# Power_Switching_Circuit_rev5.net
KiCad netlist of a schematic drawn in EAGLE
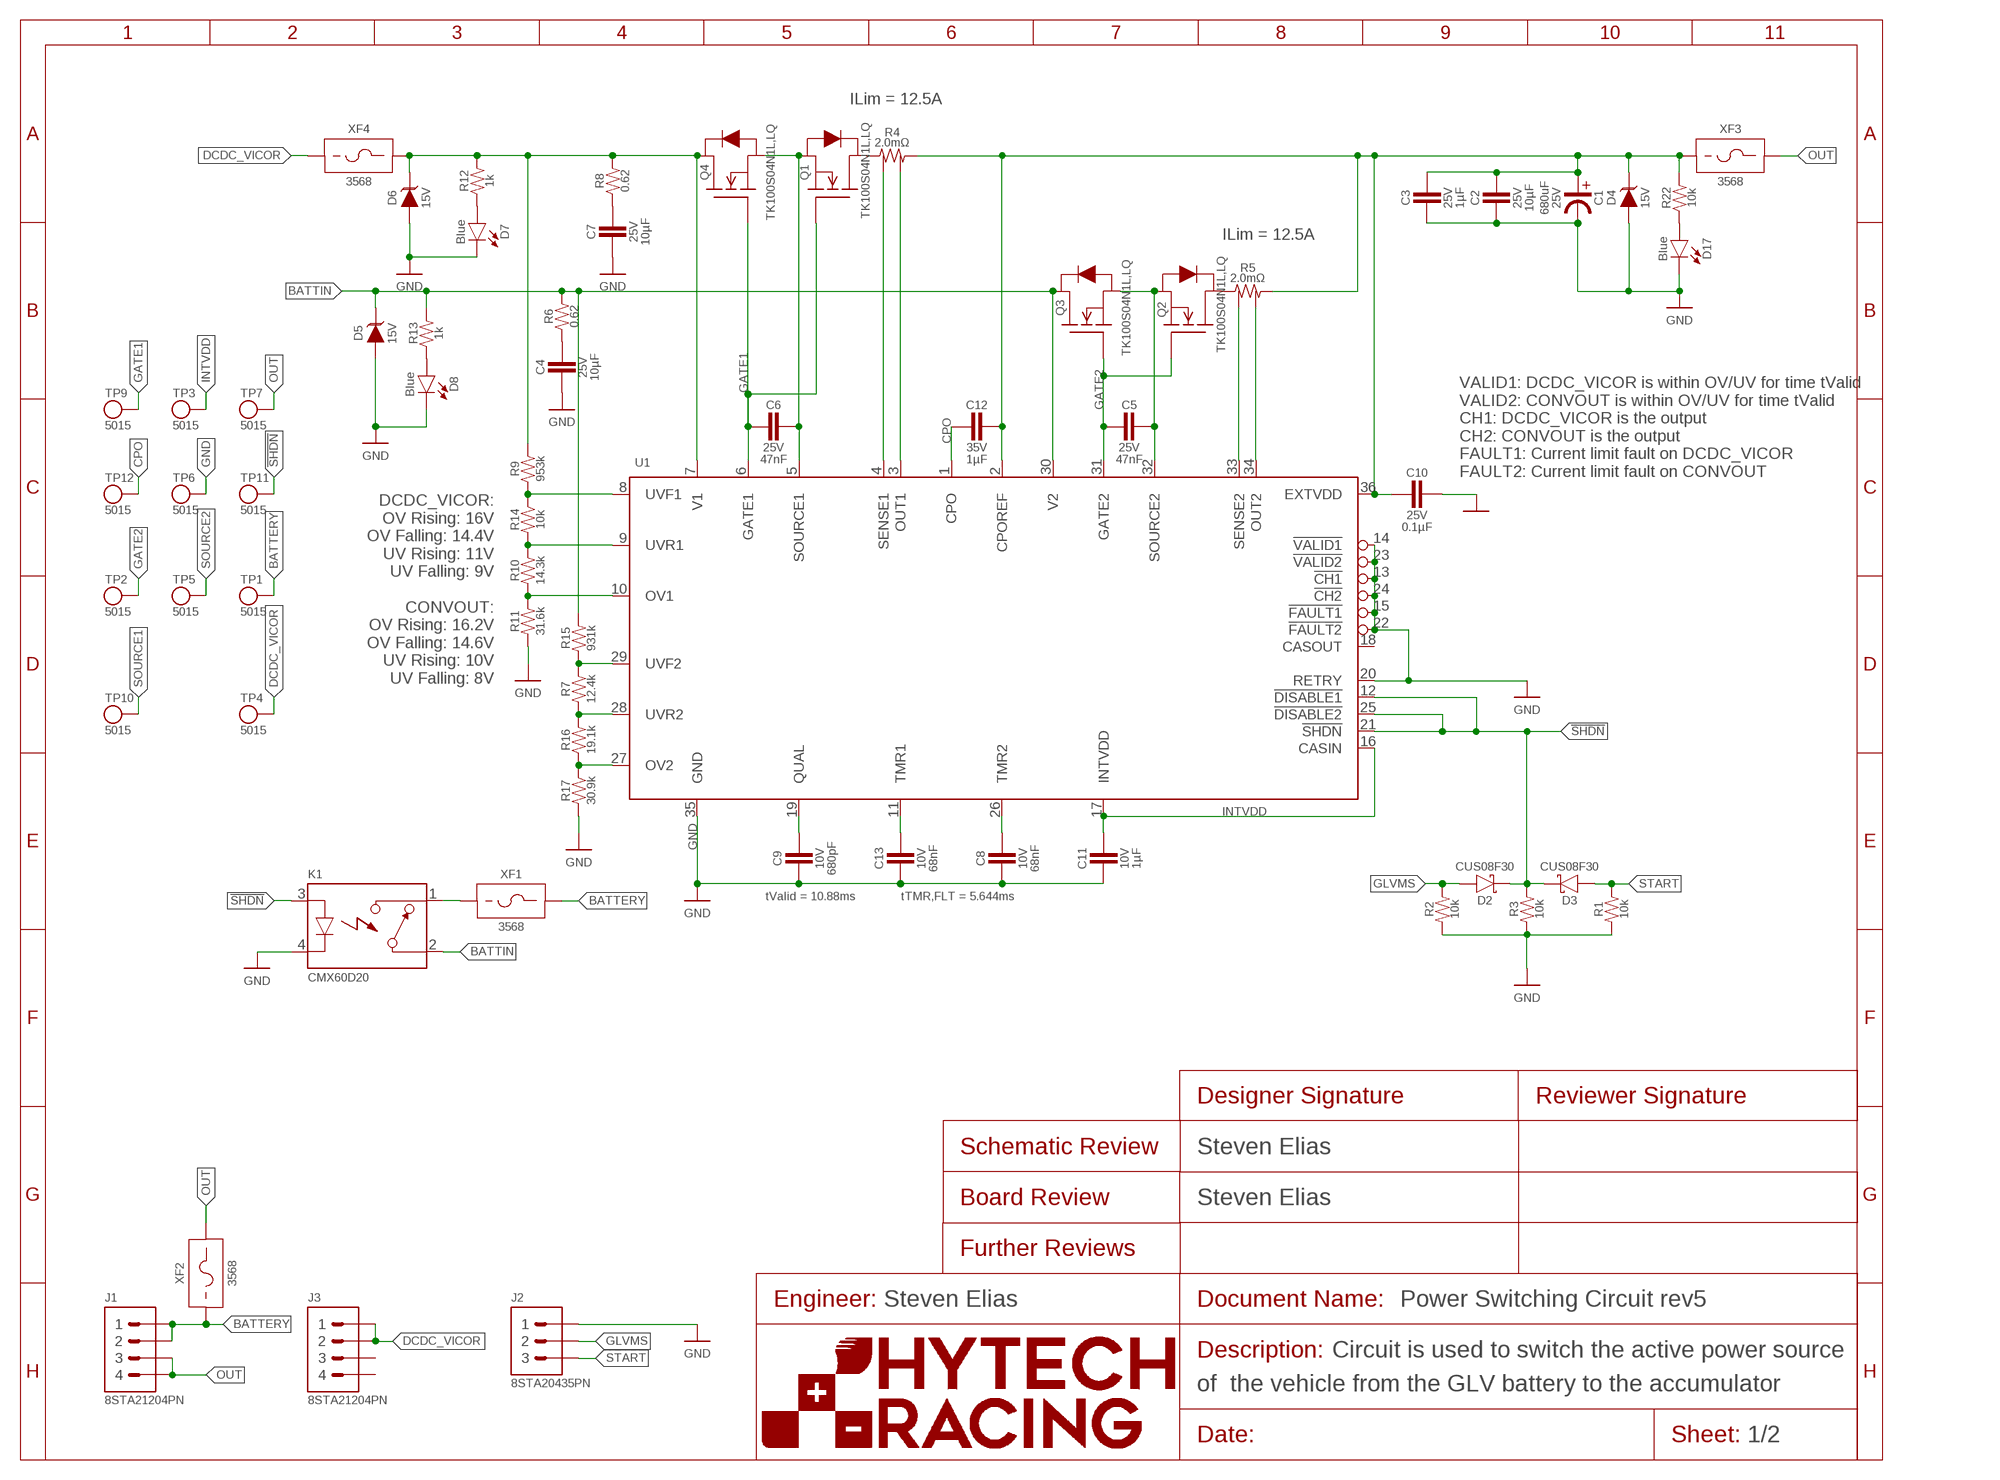
[diagram p0: schematic, sheet 1]
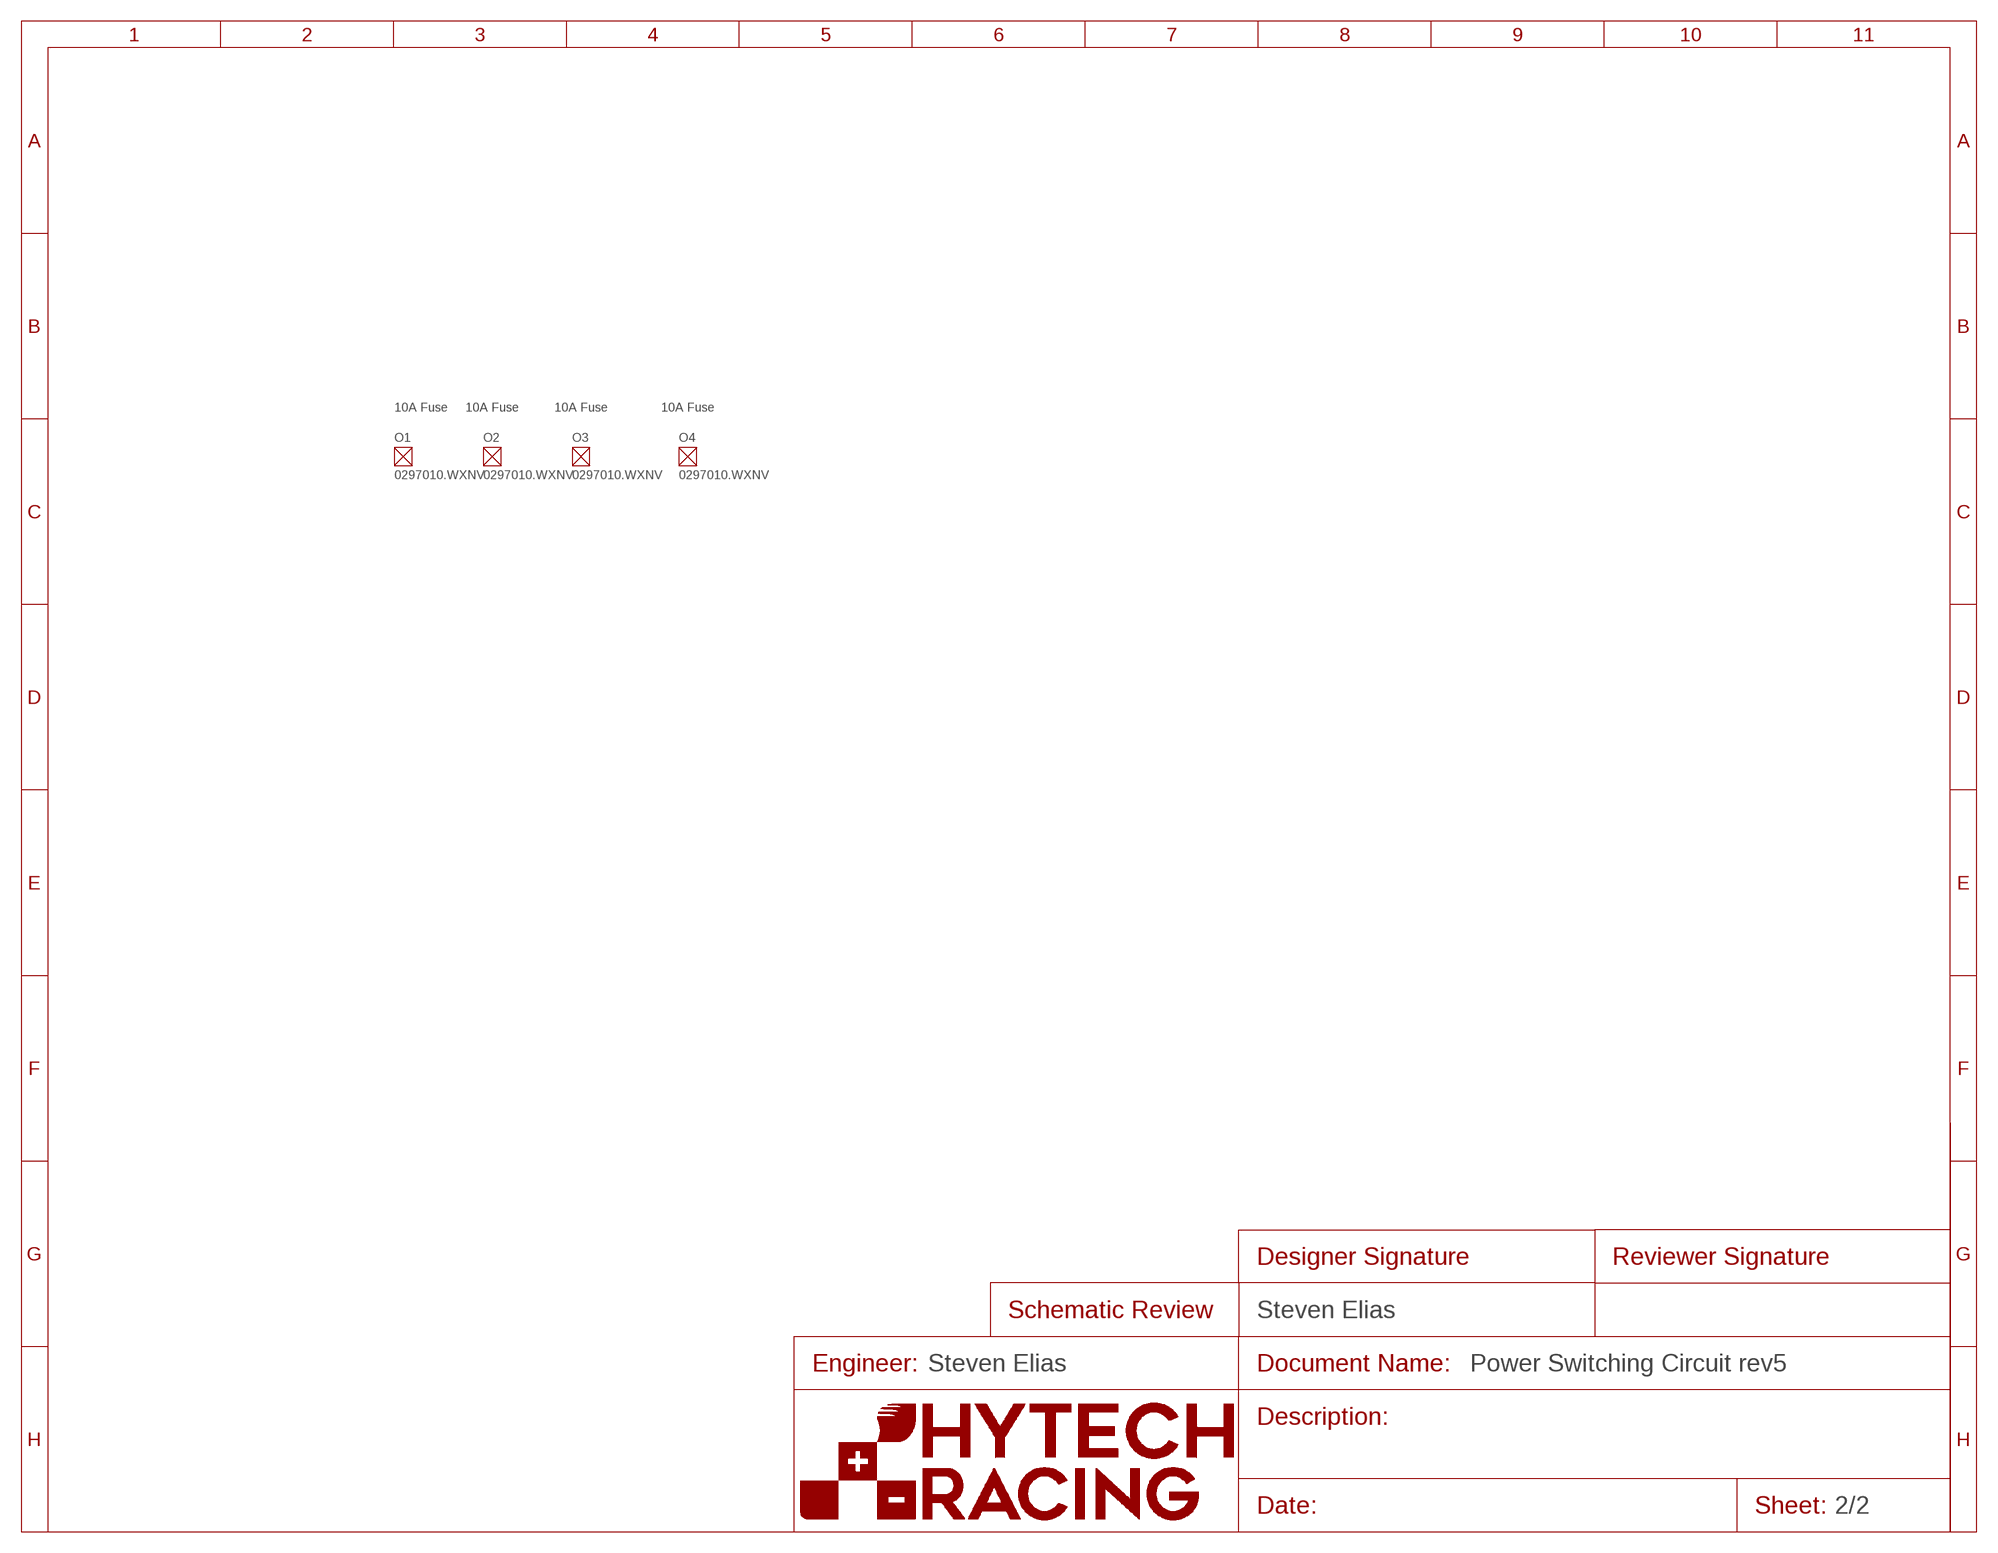
[diagram p1: schematic, sheet 2]

(export (version "E")
  (design (tool "Eeschema 10.0.6"))
  (components
    (comp (ref "C1")
      (value "EEUFP1E681")
      (footprint "eagle-import:EEUFP1E_")
      (fields
        (field (name "CAPACITANCE") "680uF")
        (field (name "MANUFACTURER") "Panasonic Electronic Components")
        (field (name "MPN") "EEU-FP1E681")
        (field (name "TOLERANCE") "20%")
        (field (name "VOLTAGE") "25V")
      )
      (libsource (lib "eagle-import") (part "EEUFP1E681"))
    )
    (comp (ref "C2")
      (value "CAPACITOR_0603_25V_10UF")
      (footprint "eagle-import:0603-CAP")
      (fields
        (field (name "CAPACITANCE") "10µF")
        (field (name "MANUFACTURER") "Murata Electronics")
        (field (name "MPN") "GRM188R61E106MA73D")
        (field (name "TOLERANCE") "20%")
        (field (name "VOLTAGE") "25V")
      )
      (libsource (lib "eagle-import") (part "CAPACITOR_?_060325V_10UF"))
    )
    (comp (ref "C3")
      (value "CAPACITOR_0603_25V_1UF")
      (footprint "eagle-import:0603-CAP")
      (fields
        (field (name "CAPACITANCE") "1µF")
        (field (name "MANUFACTURER") "Samsung Electro-Mechanics")
        (field (name "MPN") "CL10B105KA8NNNC")
        (field (name "TOLERANCE") "10%")
        (field (name "VOLTAGE") "25V")
      )
      (libsource (lib "eagle-import") (part "CAPACITOR_?_060325V_1UF"))
    )
    (comp (ref "C4")
      (value "CAPACITOR_0603_25V_10UF")
      (footprint "eagle-import:0603-CAP")
      (fields
        (field (name "CAPACITANCE") "10µF")
        (field (name "MANUFACTURER") "Murata Electronics")
        (field (name "MPN") "GRM188R61E106MA73D")
        (field (name "TOLERANCE") "20%")
        (field (name "VOLTAGE") "25V")
      )
      (libsource (lib "eagle-import") (part "CAPACITOR_?_060325V_10UF"))
    )
    (comp (ref "C5")
      (value "CAPACITOR_0603_25V_47NF")
      (footprint "eagle-import:0603-CAP")
      (fields
        (field (name "CAPACITANCE") "47nF")
        (field (name "MANUFACTURER") "Kyocera AVX")
        (field (name "MPN") "06033C473K4Z2A")
        (field (name "TOLERANCE") "10%")
        (field (name "VOLTAGE") "25V")
      )
      (libsource (lib "eagle-import") (part "CAPACITOR_?_060325V_47NF"))
    )
    (comp (ref "C6")
      (value "CAPACITOR_0603_25V_47NF")
      (footprint "eagle-import:0603-CAP")
      (fields
        (field (name "CAPACITANCE") "47nF")
        (field (name "MANUFACTURER") "Kyocera AVX")
        (field (name "MPN") "06033C473K4Z2A")
        (field (name "TOLERANCE") "10%")
        (field (name "VOLTAGE") "25V")
      )
      (libsource (lib "eagle-import") (part "CAPACITOR_?_060325V_47NF"))
    )
    (comp (ref "C7")
      (value "CAPACITOR_0603_25V_10UF")
      (footprint "eagle-import:0603-CAP")
      (fields
        (field (name "CAPACITANCE") "10µF")
        (field (name "MANUFACTURER") "Murata Electronics")
        (field (name "MPN") "GRM188R61E106MA73D")
        (field (name "TOLERANCE") "20%")
        (field (name "VOLTAGE") "25V")
      )
      (libsource (lib "eagle-import") (part "CAPACITOR_?_060325V_10UF"))
    )
    (comp (ref "C8")
      (value "CAPACITOR_0603_10V_68NF")
      (footprint "eagle-import:0603-CAP")
      (fields
        (field (name "CAPACITANCE") "68nF")
        (field (name "MANUFACTURER") "KEMET")
        (field (name "MPN") "C0603C683K8RACTU")
        (field (name "TOLERANCE") "10%")
        (field (name "VOLTAGE") "10V")
      )
      (libsource (lib "eagle-import") (part "CAPACITOR_?_060310V_68NF"))
    )
    (comp (ref "C9")
      (value "CAPACITOR_0603_10V_680PF")
      (footprint "eagle-import:0603-CAP")
      (fields
        (field (name "CAPACITANCE") "680pF")
        (field (name "MANUFACTURER") "Würth Elektronik")
        (field (name "MPN") "885012006013")
        (field (name "TOLERANCE") "5%")
        (field (name "VOLTAGE") "10V")
      )
      (libsource (lib "eagle-import") (part "CAPACITOR_?_060310V_680PF"))
    )
    (comp (ref "C10")
      (value "CAPACITOR_0603_25V_0.1UF")
      (footprint "eagle-import:0603-CAP")
      (fields
        (field (name "CAPACITANCE") "0.1µF")
        (field (name "MANUFACTURER") "Samsung Electro-Mechanics")
        (field (name "MPN") "CL10B104KA8NNNC")
        (field (name "TOLERANCE") "10%")
        (field (name "VOLTAGE") "25V")
      )
      (libsource (lib "eagle-import") (part "CAPACITOR_?_060325V_0.1UF"))
    )
    (comp (ref "C11")
      (value "CAPACITOR_0603_10V_1UF")
      (footprint "eagle-import:0603-CAP")
      (fields
        (field (name "CAPACITANCE") "1µF")
        (field (name "MANUFACTURER") "Yageo")
        (field (name "MPN") "CC0603KRX7R6BB105")
        (field (name "TOLERANCE") "10%")
        (field (name "VOLTAGE") "10V")
      )
      (libsource (lib "eagle-import") (part "CAPACITOR_?_060310V_1UF"))
    )
    (comp (ref "C12")
      (value "CAPACITOR_0603_35V_1UF")
      (footprint "eagle-import:0603-CAP")
      (fields
        (field (name "CAPACITANCE") "1µF")
        (field (name "MANUFACTURER") "TDK Corporation")
        (field (name "MPN") "C1608X7R1V105K080AE")
        (field (name "TOLERANCE") "10%")
        (field (name "VOLTAGE") "35V")
      )
      (libsource (lib "eagle-import") (part "CAPACITOR_?_060335V_1UF"))
    )
    (comp (ref "C13")
      (value "CAPACITOR_0603_10V_68NF")
      (footprint "eagle-import:0603-CAP")
      (fields
        (field (name "CAPACITANCE") "68nF")
        (field (name "MANUFACTURER") "KEMET")
        (field (name "MPN") "C0603C683K8RACTU")
        (field (name "TOLERANCE") "10%")
        (field (name "VOLTAGE") "10V")
      )
      (libsource (lib "eagle-import") (part "CAPACITOR_?_060310V_68NF"))
    )
    (comp (ref "D2")
      (value "SCHOTTKY_SOD323_30V")
      (footprint "eagle-import:SOD-323")
      (fields
        (field (name "MANUFACTURER") "Toshiba Semiconductor and Storage")
        (field (name "MPN") "CUS08F30")
        (field (name "VOLTAGE") "30V")
      )
      (libsource (lib "eagle-import") (part "SCHOTTKY_?_SOD32330V"))
    )
    (comp (ref "D3")
      (value "SCHOTTKY_SOD323_30V")
      (footprint "eagle-import:SOD-323")
      (fields
        (field (name "MANUFACTURER") "Toshiba Semiconductor and Storage")
        (field (name "MPN") "CUS08F30")
        (field (name "VOLTAGE") "30V")
      )
      (libsource (lib "eagle-import") (part "SCHOTTKY_?_SOD32330V"))
    )
    (comp (ref "D4")
      (value "TVS_15V")
      (footprint "eagle-import:SOT-23")
      (fields
        (field (name "MANUFACTURER") "Vishay General Semiconductor - Diodes Division")
        (field (name "MPN") "GSOT15-E3-08")
        (field (name "VOLTAGE") "15V")
      )
      (libsource (lib "eagle-import") (part "TVS_15V"))
    )
    (comp (ref "D5")
      (value "TVS_15V")
      (footprint "eagle-import:SOT-23")
      (fields
        (field (name "MANUFACTURER") "Vishay General Semiconductor - Diodes Division")
        (field (name "MPN") "GSOT15-E3-08")
        (field (name "VOLTAGE") "15V")
      )
      (libsource (lib "eagle-import") (part "TVS_15V"))
    )
    (comp (ref "D6")
      (value "TVS_15V")
      (footprint "eagle-import:SOT-23")
      (fields
        (field (name "MANUFACTURER") "Vishay General Semiconductor - Diodes Division")
        (field (name "MPN") "GSOT15-E3-08")
        (field (name "VOLTAGE") "15V")
      )
      (libsource (lib "eagle-import") (part "TVS_15V"))
    )
    (comp (ref "D7")
      (value "LED_0603_BLUE")
      (footprint "eagle-import:0603-LED")
      (fields
        (field (name "COLOR") "Blue")
        (field (name "MANUFACTURER") "Kingbright")
        (field (name "MPN") "APT1608VBC/D")
      )
      (libsource (lib "eagle-import") (part "LED_?_0603BLUE"))
    )
    (comp (ref "D8")
      (value "LED_0603_BLUE")
      (footprint "eagle-import:0603-LED")
      (fields
        (field (name "COLOR") "Blue")
        (field (name "MANUFACTURER") "Kingbright")
        (field (name "MPN") "APT1608VBC/D")
      )
      (libsource (lib "eagle-import") (part "LED_?_0603BLUE"))
    )
    (comp (ref "D17")
      (value "LED_0603_BLUE")
      (footprint "eagle-import:0603-LED")
      (fields
        (field (name "COLOR") "Blue")
        (field (name "MANUFACTURER") "Kingbright")
        (field (name "MPN") "APT1608VBC/D")
      )
      (libsource (lib "eagle-import") (part "LED_?_0603BLUE"))
    )
    (comp (ref "J1")
      (value "CONNECTOR-4_SOURIAU_")
      (footprint "eagle-import:SOURIAU_12-04")
      (fields (field (name "MPN") "8STA21204PN") (field (name "MANUFACTURER") "Souriau"))
      (libsource (lib "eagle-import") (part "CONNECTOR-4_?_SOURIAU"))
    )
    (comp (ref "J2")
      (value "CONNECTOR-3_8STA20435PN")
      (footprint "eagle-import:SOURIAU_04-35")
      (fields (field (name "MANUFACTURER") "Souriau") (field (name "MPN") "8STA20435PN"))
      (libsource (lib "eagle-import") (part "CONNECTOR-3_?8STA20435PN"))
    )
    (comp (ref "J3")
      (value "CONNECTOR-4_SOURIAU_")
      (footprint "eagle-import:SOURIAU_12-04")
      (fields (field (name "MPN") "8STA21204PN") (field (name "MANUFACTURER") "Souriau"))
      (libsource (lib "eagle-import") (part "CONNECTOR-4_?_SOURIAU"))
    )
    (comp (ref "K1")
      (value "RELAY_SOLIDSTATE_NO_CMX60D20")
      (footprint "eagle-import:CRYDOM_CMX")
      (fields (field (name "MANUFACTURER") "Crydom") (field (name "MPN") "CMX60D20"))
      (libsource (lib "eagle-import") (part "RELAY_SOLIDSTATE_NO_?CMX60D20"))
    )
    (comp (ref "Q1")
      (value "TRANSISTOR_N_MOS_2-7K1S_TK100S04N1LLQ")
      (footprint "eagle-import:DPAK(2-7K1S)")
      (fields
        (field (name "MANUFACTURER") "Toshiba Semiconductor and Storage")
        (field (name "MPN") "TK100S04N1L,LQ")
      )
      (libsource (lib "eagle-import") (part "TRANSISTOR_N_MOS_?_2-7K1STK100S04N1LLQ"))
    )
    (comp (ref "Q2")
      (value "TRANSISTOR_N_MOS_2-7K1S_TK100S04N1LLQ")
      (footprint "eagle-import:DPAK(2-7K1S)")
      (fields
        (field (name "MANUFACTURER") "Toshiba Semiconductor and Storage")
        (field (name "MPN") "TK100S04N1L,LQ")
      )
      (libsource (lib "eagle-import") (part "TRANSISTOR_N_MOS_?_2-7K1STK100S04N1LLQ"))
    )
    (comp (ref "Q3")
      (value "TRANSISTOR_N_MOS_2-7K1S_TK100S04N1LLQ")
      (footprint "eagle-import:DPAK(2-7K1S)")
      (fields
        (field (name "MANUFACTURER") "Toshiba Semiconductor and Storage")
        (field (name "MPN") "TK100S04N1L,LQ")
      )
      (libsource (lib "eagle-import") (part "TRANSISTOR_N_MOS_?_2-7K1STK100S04N1LLQ"))
    )
    (comp (ref "Q4")
      (value "TRANSISTOR_N_MOS_2-7K1S_TK100S04N1LLQ")
      (footprint "eagle-import:DPAK(2-7K1S)")
      (fields
        (field (name "MANUFACTURER") "Toshiba Semiconductor and Storage")
        (field (name "MPN") "TK100S04N1L,LQ")
      )
      (libsource (lib "eagle-import") (part "TRANSISTOR_N_MOS_?_2-7K1STK100S04N1LLQ"))
    )
    (comp (ref "R1")
      (value "RESISTOR_0603_10K")
      (footprint "eagle-import:0603-RES")
      (fields
        (field (name "MANUFACTURER") "Yageo")
        (field (name "MPN") "RC0603FR-0710KL")
        (field (name "POWER") "0.1W")
        (field (name "RESISTANCE") "10k")
      )
      (libsource (lib "eagle-import") (part "RESISTOR_?_060310K"))
    )
    (comp (ref "R2")
      (value "RESISTOR_0603_10K")
      (footprint "eagle-import:0603-RES")
      (fields
        (field (name "MANUFACTURER") "Yageo")
        (field (name "MPN") "RC0603FR-0710KL")
        (field (name "POWER") "0.1W")
        (field (name "RESISTANCE") "10k")
      )
      (libsource (lib "eagle-import") (part "RESISTOR_?_060310K"))
    )
    (comp (ref "R3")
      (value "RESISTOR_0603_10K")
      (footprint "eagle-import:0603-RES")
      (fields
        (field (name "MANUFACTURER") "Yageo")
        (field (name "MPN") "RC0603FR-0710KL")
        (field (name "POWER") "0.1W")
        (field (name "RESISTANCE") "10k")
      )
      (libsource (lib "eagle-import") (part "RESISTOR_?_060310K"))
    )
    (comp (ref "R4")
      (value "RESISTOR_SENSE__WSL40262L000FEB")
      (footprint "eagle-import:4026")
      (fields
        (field (name "MANUFACTURER") "Vishay Dale")
        (field (name "MPN") "WSL40262L000FEB")
        (field (name "POWER") "3W")
        (field (name "RESISTANCE") "2.0mΩ")
      )
      (libsource (lib "eagle-import") (part "RESISTOR_SENSE_?_WSL40262L000FEB"))
    )
    (comp (ref "R5")
      (value "RESISTOR_SENSE__WSL40262L000FEB")
      (footprint "eagle-import:4026")
      (fields
        (field (name "MANUFACTURER") "Vishay Dale")
        (field (name "MPN") "WSL40262L000FEB")
        (field (name "POWER") "3W")
        (field (name "RESISTANCE") "2.0mΩ")
      )
      (libsource (lib "eagle-import") (part "RESISTOR_SENSE_?_WSL40262L000FEB"))
    )
    (comp (ref "R6")
      (value "RESISTOR_0805_0.62")
      (footprint "eagle-import:0805-RES")
      (fields
        (field (name "MANUFACTURER") "Yageo")
        (field (name "MPN") "RL0805FR-070R62L")
        (field (name "POWER") "0.125W")
        (field (name "RESISTANCE") "0.62")
      )
      (libsource (lib "eagle-import") (part "RESISTOR_?_08050.62"))
    )
    (comp (ref "R7")
      (value "RESISTOR_0603_12.4K")
      (footprint "eagle-import:0603-RES")
      (fields
        (field (name "MANUFACTURER") "Panasonic Electronic Components")
        (field (name "MPN") "ERJ-PB3B1242V")
        (field (name "POWER") "0.2W")
        (field (name "RESISTANCE") "12.4k")
      )
      (libsource (lib "eagle-import") (part "RESISTOR_?_060312.4K"))
    )
    (comp (ref "R8")
      (value "RESISTOR_0805_0.62")
      (footprint "eagle-import:0805-RES")
      (fields
        (field (name "MANUFACTURER") "Yageo")
        (field (name "MPN") "RL0805FR-070R62L")
        (field (name "POWER") "0.125W")
        (field (name "RESISTANCE") "0.62")
      )
      (libsource (lib "eagle-import") (part "RESISTOR_?_08050.62"))
    )
    (comp (ref "R9")
      (value "RESISTOR_0805_953K")
      (footprint "eagle-import:0805-RES")
      (fields
        (field (name "MANUFACTURER") "Panasonic Electronic Components")
        (field (name "MPN") "ERJ-6ENF9533V")
        (field (name "POWER") "0.125W")
        (field (name "RESISTANCE") "953k")
      )
      (libsource (lib "eagle-import") (part "RESISTOR_?_0805953K"))
    )
    (comp (ref "R10")
      (value "RESISTOR_0805_14.3K")
      (footprint "eagle-import:0805-RES")
      (fields
        (field (name "MANUFACTURER") "Panasonic Electronic Components")
        (field (name "MPN") "ERJ-6ENF1432V")
        (field (name "POWER") "0.125W")
        (field (name "RESISTANCE") "14.3k")
      )
      (libsource (lib "eagle-import") (part "RESISTOR_?_080514.3K"))
    )
    (comp (ref "R11")
      (value "RESISTOR_0805_31.6K")
      (footprint "eagle-import:0805-RES")
      (fields
        (field (name "MANUFACTURER") "Vishay Dale")
        (field (name "MPN") "CRCW060331K6FKEAHP")
        (field (name "POWER") "0.33W")
        (field (name "RESISTANCE") "31.6k")
      )
      (libsource (lib "eagle-import") (part "RESISTOR_?_080531.6K"))
    )
    (comp (ref "R12")
      (value "RESISTOR_0603_1K")
      (footprint "eagle-import:0603-RES")
      (fields
        (field (name "MANUFACTURER") "Yageo")
        (field (name "MPN") "RC0603FR-071KL")
        (field (name "POWER") "0.1W")
        (field (name "RESISTANCE") "1k")
      )
      (libsource (lib "eagle-import") (part "RESISTOR_?_06031K"))
    )
    (comp (ref "R13")
      (value "RESISTOR_0603_1K")
      (footprint "eagle-import:0603-RES")
      (fields
        (field (name "MANUFACTURER") "Yageo")
        (field (name "MPN") "RC0603FR-071KL")
        (field (name "POWER") "0.1W")
        (field (name "RESISTANCE") "1k")
      )
      (libsource (lib "eagle-import") (part "RESISTOR_?_06031K"))
    )
    (comp (ref "R14")
      (value "RESISTOR_0603_10K")
      (footprint "eagle-import:0603-RES")
      (fields
        (field (name "MANUFACTURER") "Yageo")
        (field (name "MPN") "RC0603FR-0710KL")
        (field (name "POWER") "0.1W")
        (field (name "RESISTANCE") "10k")
      )
      (libsource (lib "eagle-import") (part "RESISTOR_?_060310K"))
    )
    (comp (ref "R15")
      (value "RESISTOR_0805_931K")
      (footprint "eagle-import:0805-RES")
      (fields
        (field (name "MANUFACTURER") "Panasonic Electronic Components")
        (field (name "MPN") "ERJ-PB6B9313V")
        (field (name "POWER") "0.25W")
        (field (name "RESISTANCE") "931k")
      )
      (libsource (lib "eagle-import") (part "RESISTOR_?_0805931K"))
    )
    (comp (ref "R16")
      (value "RESISTOR_0805_19.1K")
      (footprint "eagle-import:0805-RES")
      (fields
        (field (name "MANUFACTURER") "Panasonic Electronic Components")
        (field (name "MPN") "ERJ-6ENF1912V")
        (field (name "POWER") "0.125W")
        (field (name "RESISTANCE") "19.1k")
      )
      (libsource (lib "eagle-import") (part "RESISTOR_?_080519.1K"))
    )
    (comp (ref "R17")
      (value "RESISTOR_0603_30.9K")
      (footprint "eagle-import:0603-RES")
      (fields
        (field (name "MANUFACTURER") "Panasonic Electronic Components")
        (field (name "MPN") "ERJ-PB3B3092V")
        (field (name "POWER") "0.25W")
        (field (name "RESISTANCE") "30.9k")
      )
      (libsource (lib "eagle-import") (part "RESISTOR_?_060330.9K"))
    )
    (comp (ref "R22")
      (value "RESISTOR_0603_10K")
      (footprint "eagle-import:0603-RES")
      (fields
        (field (name "MANUFACTURER") "Yageo")
        (field (name "MPN") "RC0603FR-0710KL")
        (field (name "POWER") "0.1W")
        (field (name "RESISTANCE") "10k")
      )
      (libsource (lib "eagle-import") (part "RESISTOR_?_060310K"))
    )
    (comp (ref "TP1")
      (value "TEST_POINT")
      (footprint "eagle-import:5015")
      (fields (field (name "MPN") "5015") (field (name "MANUFACTURER") "Keystone Electronics"))
      (libsource (lib "eagle-import") (part "TEST_POINT"))
    )
    (comp (ref "TP2")
      (value "TEST_POINT")
      (footprint "eagle-import:5015")
      (fields (field (name "MPN") "5015") (field (name "MANUFACTURER") "Keystone Electronics"))
      (libsource (lib "eagle-import") (part "TEST_POINT"))
    )
    (comp (ref "TP3")
      (value "INTVDD")
      (footprint "eagle-import:5015")
      (fields (field (name "MPN") "5015") (field (name "MANUFACTURER") "Keystone Electronics"))
      (libsource (lib "eagle-import") (part "TEST_POINT"))
    )
    (comp (ref "TP4")
      (value "TEST_POINT")
      (footprint "eagle-import:5015")
      (fields (field (name "MPN") "5015") (field (name "MANUFACTURER") "Keystone Electronics"))
      (libsource (lib "eagle-import") (part "TEST_POINT"))
    )
    (comp (ref "TP5")
      (value "TEST_POINT")
      (footprint "eagle-import:5015")
      (fields (field (name "MPN") "5015") (field (name "MANUFACTURER") "Keystone Electronics"))
      (libsource (lib "eagle-import") (part "TEST_POINT"))
    )
    (comp (ref "TP6")
      (value "TEST_POINT")
      (footprint "eagle-import:5015")
      (fields (field (name "MPN") "5015") (field (name "MANUFACTURER") "Keystone Electronics"))
      (libsource (lib "eagle-import") (part "TEST_POINT"))
    )
    (comp (ref "TP7")
      (value "TEST_POINT")
      (footprint "eagle-import:5015")
      (fields (field (name "MPN") "5015") (field (name "MANUFACTURER") "Keystone Electronics"))
      (libsource (lib "eagle-import") (part "TEST_POINT"))
    )
    (comp (ref "TP9")
      (value "TEST_POINT")
      (footprint "eagle-import:5015")
      (fields (field (name "MPN") "5015") (field (name "MANUFACTURER") "Keystone Electronics"))
      (libsource (lib "eagle-import") (part "TEST_POINT"))
    )
    (comp (ref "TP10")
      (value "TEST_POINT")
      (footprint "eagle-import:5015")
      (fields (field (name "MPN") "5015") (field (name "MANUFACTURER") "Keystone Electronics"))
      (libsource (lib "eagle-import") (part "TEST_POINT"))
    )
    (comp (ref "TP11")
      (value "TEST_POINT")
      (footprint "eagle-import:5015")
      (fields (field (name "MPN") "5015") (field (name "MANUFACTURER") "Keystone Electronics"))
      (libsource (lib "eagle-import") (part "TEST_POINT"))
    )
    (comp (ref "TP12")
      (value "TEST_POINT")
      (footprint "eagle-import:5015")
      (fields (field (name "MPN") "5015") (field (name "MANUFACTURER") "Keystone Electronics"))
      (libsource (lib "eagle-import") (part "TEST_POINT"))
    )
    (comp (ref "U1")
      (value "LTC4421")
      (footprint "eagle-import:SSOP-36")
      (fields (field (name "MPN") "LTC4421CG#PBF") (field (name "MANUFACTURER") "Analog Devices Inc."))
      (libsource (lib "eagle-import") (part "LTC4421"))
    )
    (comp (ref "XF1")
      (value "FUSE_HOLDER_MINIBLADEPTH")
      (footprint "eagle-import:3568")
      (fields (field (name "MANUFACTURER") "Keystone") (field (name "MPN") "3568"))
      (libsource (lib "eagle-import") (part "FUSE_HOLDER_PTHMINIBLADE"))
    )
    (comp (ref "XF2")
      (value "FUSE_HOLDER_MINIBLADEPTH")
      (footprint "eagle-import:3568")
      (fields (field (name "MANUFACTURER") "Keystone") (field (name "MPN") "3568"))
      (libsource (lib "eagle-import") (part "FUSE_HOLDER_PTHMINIBLADE"))
    )
    (comp (ref "XF3")
      (value "FUSE_HOLDER_MINIBLADEPTH")
      (footprint "eagle-import:3568")
      (fields (field (name "MANUFACTURER") "Keystone") (field (name "MPN") "3568"))
      (libsource (lib "eagle-import") (part "FUSE_HOLDER_PTHMINIBLADE"))
    )
    (comp (ref "XF4")
      (value "FUSE_HOLDER_MINIBLADEPTH")
      (footprint "eagle-import:3568")
      (fields (field (name "MANUFACTURER") "Keystone") (field (name "MPN") "3568"))
      (libsource (lib "eagle-import") (part "FUSE_HOLDER_PTHMINIBLADE"))
    )
  )
  (nets
    (net (code "1") (name "BATTERY") (class "Default")
      (node (ref "J1") (pin "1") (pinfunction "1_1") (pintype "passive"))
      (node (ref "J1") (pin "2") (pinfunction "2_2") (pintype "passive"))
      (node (ref "TP1") (pin "1") (pinfunction "1_1") (pintype "passive"))
      (node (ref "XF1") (pin "3") (pinfunction "2_3") (pintype "passive"))
      (node (ref "XF1") (pin "4") (pinfunction "2_4") (pintype "passive"))
      (node (ref "XF2") (pin "1") (pinfunction "1_1") (pintype "passive"))
      (node (ref "XF2") (pin "2") (pinfunction "1_2") (pintype "passive"))
    )
    (net (code "2") (name "BATTIN") (class "Default")
      (node (ref "D5") (pin "3") (pinfunction "C_3") (pintype "passive"))
      (node (ref "K1") (pin "2") (pinfunction "CONTACT1_2") (pintype "bidirectional"))
      (node (ref "Q3") (pin "2") (pinfunction "D_2") (pintype "passive"))
      (node (ref "R13") (pin "2") (pinfunction "2_2") (pintype "passive"))
      (node (ref "R15") (pin "2") (pinfunction "2_2") (pintype "passive"))
      (node (ref "R6") (pin "2") (pinfunction "2_2") (pintype "passive"))
      (node (ref "U1") (pin "30") (pinfunction "V2_30") (pintype "input"))
    )
    (net (code "3") (name "CPO") (class "Default")
      (node (ref "C12") (pin "2") (pinfunction "2_2") (pintype "passive"))
      (node (ref "TP12") (pin "1") (pinfunction "1_1") (pintype "passive"))
      (node (ref "U1") (pin "1") (pinfunction "CPO_1") (pintype "input"))
    )
    (net (code "4") (name "DCDC_VICOR") (class "Default")
      (node (ref "J3") (pin "1") (pinfunction "1_1") (pintype "passive"))
      (node (ref "J3") (pin "2") (pinfunction "2_2") (pintype "passive"))
      (node (ref "TP4") (pin "1") (pinfunction "1_1") (pintype "passive"))
      (node (ref "XF4") (pin "1") (pinfunction "1_1") (pintype "passive"))
      (node (ref "XF4") (pin "2") (pinfunction "1_2") (pintype "passive"))
    )
    (net (code "5") (name "GATE1") (class "Default")
      (node (ref "C6") (pin "2") (pinfunction "2_2") (pintype "passive"))
      (node (ref "Q1") (pin "1") (pinfunction "G_1") (pintype "passive"))
      (node (ref "Q4") (pin "1") (pinfunction "G_1") (pintype "passive"))
      (node (ref "TP9") (pin "1") (pinfunction "1_1") (pintype "passive"))
      (node (ref "U1") (pin "6") (pinfunction "GATE1_6") (pintype "output"))
    )
    (net (code "6") (name "GATE2") (class "Default")
      (node (ref "C5") (pin "2") (pinfunction "2_2") (pintype "passive"))
      (node (ref "Q2") (pin "1") (pinfunction "G_1") (pintype "passive"))
      (node (ref "Q3") (pin "1") (pinfunction "G_1") (pintype "passive"))
      (node (ref "TP2") (pin "1") (pinfunction "1_1") (pintype "passive"))
      (node (ref "U1") (pin "31") (pinfunction "GATE2_31") (pintype "output"))
    )
    (net (code "7") (name "GLVMS") (class "Default")
      (node (ref "D2") (pin "A") (pinfunction "A_A") (pintype "passive"))
      (node (ref "J2") (pin "B") (pinfunction "2_B") (pintype "passive"))
      (node (ref "R2") (pin "2") (pinfunction "2_2") (pintype "passive"))
    )
    (net (code "8") (name "GND") (class "Default")
      (node (ref "C1") (pin "P$2") (pinfunction "MINUS_P$2") (pintype "passive"))
      (node (ref "C10") (pin "1") (pinfunction "1_1") (pintype "passive"))
      (node (ref "C11") (pin "2") (pinfunction "2_2") (pintype "passive"))
      (node (ref "C13") (pin "2") (pinfunction "2_2") (pintype "passive"))
      (node (ref "C2") (pin "2") (pinfunction "2_2") (pintype "passive"))
      (node (ref "C3") (pin "2") (pinfunction "2_2") (pintype "passive"))
      (node (ref "C4") (pin "2") (pinfunction "2_2") (pintype "passive"))
      (node (ref "C7") (pin "2") (pinfunction "2_2") (pintype "passive"))
      (node (ref "C8") (pin "2") (pinfunction "2_2") (pintype "passive"))
      (node (ref "C9") (pin "2") (pinfunction "2_2") (pintype "passive"))
      (node (ref "D17") (pin "1") (pinfunction "C_1") (pintype "passive"))
      (node (ref "D4") (pin "1") (pinfunction "A_1") (pintype "passive"))
      (node (ref "D5") (pin "1") (pinfunction "A_1") (pintype "passive"))
      (node (ref "D6") (pin "1") (pinfunction "A_1") (pintype "passive"))
      (node (ref "D7") (pin "1") (pinfunction "C_1") (pintype "passive"))
      (node (ref "D8") (pin "1") (pinfunction "C_1") (pintype "passive"))
      (node (ref "J2") (pin "A") (pinfunction "1_A") (pintype "passive"))
      (node (ref "K1") (pin "4") (pinfunction "CONTROL-_4") (pintype "passive"))
      (node (ref "R1") (pin "1") (pinfunction "1_1") (pintype "passive"))
      (node (ref "R11") (pin "1") (pinfunction "1_1") (pintype "passive"))
      (node (ref "R17") (pin "1") (pinfunction "1_1") (pintype "passive"))
      (node (ref "R2") (pin "1") (pinfunction "1_1") (pintype "passive"))
      (node (ref "R3") (pin "1") (pinfunction "1_1") (pintype "passive"))
      (node (ref "TP6") (pin "1") (pinfunction "1_1") (pintype "passive"))
      (node (ref "U1") (pin "13") (pinfunction "~{CH1}_13") (pintype "open_collector"))
      (node (ref "U1") (pin "14") (pinfunction "~{VALID1}_14") (pintype "open_collector"))
      (node (ref "U1") (pin "15") (pinfunction "~{FAULT1}_15") (pintype "open_collector"))
      (node (ref "U1") (pin "20") (pinfunction "RETRY_20") (pintype "input"))
      (node (ref "U1") (pin "22") (pinfunction "~{FAULT2}_22") (pintype "open_collector"))
      (node (ref "U1") (pin "23") (pinfunction "~{VALID2}_23") (pintype "open_collector"))
      (node (ref "U1") (pin "24") (pinfunction "~{CH2}_24") (pintype "open_collector"))
      (node (ref "U1") (pin "35") (pinfunction "GND_35") (pintype "power_in"))
    )
    (net (code "9") (name "INTVDD") (class "Default")
      (node (ref "C11") (pin "1") (pinfunction "1_1") (pintype "passive"))
      (node (ref "TP3") (pin "1") (pinfunction "1_1") (pintype "passive"))
      (node (ref "U1") (pin "16") (pinfunction "CASIN_16") (pintype "input"))
      (node (ref "U1") (pin "17") (pinfunction "INTVDD_17") (pintype "power_in"))
    )
    (net (code "10") (name "Net-(C1-PLUS)") (class "Default")
      (node (ref "C1") (pin "P$1") (pinfunction "PLUS_P$1") (pintype "passive"))
      (node (ref "C10") (pin "2") (pinfunction "2_2") (pintype "passive"))
      (node (ref "C12") (pin "1") (pinfunction "1_1") (pintype "passive"))
      (node (ref "C2") (pin "1") (pinfunction "1_1") (pintype "passive"))
      (node (ref "C3") (pin "1") (pinfunction "1_1") (pintype "passive"))
      (node (ref "D4") (pin "3") (pinfunction "C_3") (pintype "passive"))
      (node (ref "R22") (pin "2") (pinfunction "2_2") (pintype "passive"))
      (node (ref "R4") (pin "2") (pinfunction "2_2") (pintype "passive"))
      (node (ref "R5") (pin "2") (pinfunction "2_2") (pintype "passive"))
      (node (ref "U1") (pin "2") (pinfunction "CPOREF_2") (pintype "input"))
      (node (ref "U1") (pin "36") (pinfunction "EXTVDD_36") (pintype "power_in"))
      (node (ref "XF3") (pin "1") (pinfunction "1_1") (pintype "passive"))
      (node (ref "XF3") (pin "2") (pinfunction "1_2") (pintype "passive"))
    )
    (net (code "11") (name "Net-(C4-Pad1)") (class "Default")
      (node (ref "C4") (pin "1") (pinfunction "1_1") (pintype "passive"))
      (node (ref "R6") (pin "1") (pinfunction "1_1") (pintype "passive"))
    )
    (net (code "12") (name "Net-(C7-Pad1)") (class "Default")
      (node (ref "C7") (pin "1") (pinfunction "1_1") (pintype "passive"))
      (node (ref "R8") (pin "1") (pinfunction "1_1") (pintype "passive"))
    )
    (net (code "13") (name "Net-(D6-C)") (class "Default")
      (node (ref "D6") (pin "3") (pinfunction "C_3") (pintype "passive"))
      (node (ref "Q4") (pin "2") (pinfunction "D_2") (pintype "passive"))
      (node (ref "R12") (pin "2") (pinfunction "2_2") (pintype "passive"))
      (node (ref "R8") (pin "2") (pinfunction "2_2") (pintype "passive"))
      (node (ref "R9") (pin "2") (pinfunction "2_2") (pintype "passive"))
      (node (ref "U1") (pin "7") (pinfunction "V1_7") (pintype "input"))
      (node (ref "XF4") (pin "3") (pinfunction "2_3") (pintype "passive"))
      (node (ref "XF4") (pin "4") (pinfunction "2_4") (pintype "passive"))
    )
    (net (code "14") (name "Net-(D7-A)") (class "Default")
      (node (ref "D7") (pin "2") (pinfunction "A_2") (pintype "passive"))
      (node (ref "R12") (pin "1") (pinfunction "1_1") (pintype "passive"))
    )
    (net (code "15") (name "Net-(D8-A)") (class "Default")
      (node (ref "D8") (pin "2") (pinfunction "A_2") (pintype "passive"))
      (node (ref "R13") (pin "1") (pinfunction "1_1") (pintype "passive"))
    )
    (net (code "16") (name "Net-(D17-A)") (class "Default")
      (node (ref "D17") (pin "2") (pinfunction "A_2") (pintype "passive"))
      (node (ref "R22") (pin "1") (pinfunction "1_1") (pintype "passive"))
    )
    (net (code "17") (name "Net-(K1-CONTACT2)") (class "Default")
      (node (ref "K1") (pin "1") (pinfunction "CONTACT2_1") (pintype "bidirectional"))
      (node (ref "XF1") (pin "1") (pinfunction "1_1") (pintype "passive"))
      (node (ref "XF1") (pin "2") (pinfunction "1_2") (pintype "passive"))
    )
    (net (code "18") (name "Net-(Q1-D)") (class "Default")
      (node (ref "Q1") (pin "2") (pinfunction "D_2") (pintype "passive"))
      (node (ref "R4") (pin "1") (pinfunction "1_1") (pintype "passive"))
    )
    (net (code "19") (name "Net-(Q2-D)") (class "Default")
      (node (ref "Q2") (pin "2") (pinfunction "D_2") (pintype "passive"))
      (node (ref "R5") (pin "1") (pinfunction "1_1") (pintype "passive"))
    )
    (net (code "20") (name "Net-(U1-OUT1)") (class "Default")
      (node (ref "R4") (pin "4") (pinfunction "4_4") (pintype "passive"))
      (node (ref "U1") (pin "3") (pinfunction "OUT1_3") (pintype "input"))
    )
    (net (code "21") (name "Net-(U1-OUT2)") (class "Default")
      (node (ref "R5") (pin "4") (pinfunction "4_4") (pintype "passive"))
      (node (ref "U1") (pin "34") (pinfunction "OUT2_34") (pintype "input"))
    )
    (net (code "22") (name "Net-(U1-OV1)") (class "Default")
      (node (ref "R10") (pin "1") (pinfunction "1_1") (pintype "passive"))
      (node (ref "R11") (pin "2") (pinfunction "2_2") (pintype "passive"))
      (node (ref "U1") (pin "10") (pinfunction "OV1_10") (pintype "input"))
    )
    (net (code "23") (name "Net-(U1-OV2)") (class "Default")
      (node (ref "R16") (pin "1") (pinfunction "1_1") (pintype "passive"))
      (node (ref "R17") (pin "2") (pinfunction "2_2") (pintype "passive"))
      (node (ref "U1") (pin "27") (pinfunction "OV2_27") (pintype "input"))
    )
    (net (code "24") (name "Net-(U1-QUAL)") (class "Default")
      (node (ref "C9") (pin "1") (pinfunction "1_1") (pintype "passive"))
      (node (ref "U1") (pin "19") (pinfunction "QUAL_19") (pintype "bidirectional"))
    )
    (net (code "25") (name "Net-(U1-SENSE1)") (class "Default")
      (node (ref "R4") (pin "3") (pinfunction "3_3") (pintype "passive"))
      (node (ref "U1") (pin "4") (pinfunction "SENSE1_4") (pintype "input"))
    )
    (net (code "26") (name "Net-(U1-SENSE2)") (class "Default")
      (node (ref "R5") (pin "3") (pinfunction "3_3") (pintype "passive"))
      (node (ref "U1") (pin "33") (pinfunction "SENSE2_33") (pintype "input"))
    )
    (net (code "27") (name "Net-(U1-TMR1)") (class "Default")
      (node (ref "C13") (pin "1") (pinfunction "1_1") (pintype "passive"))
      (node (ref "U1") (pin "11") (pinfunction "TMR1_11") (pintype "bidirectional"))
    )
    (net (code "28") (name "Net-(U1-TMR2)") (class "Default")
      (node (ref "C8") (pin "1") (pinfunction "1_1") (pintype "passive"))
      (node (ref "U1") (pin "26") (pinfunction "TMR2_26") (pintype "bidirectional"))
    )
    (net (code "29") (name "Net-(U1-UVF1)") (class "Default")
      (node (ref "R14") (pin "2") (pinfunction "2_2") (pintype "passive"))
      (node (ref "R9") (pin "1") (pinfunction "1_1") (pintype "passive"))
      (node (ref "U1") (pin "8") (pinfunction "UVF1_8") (pintype "input"))
    )
    (net (code "30") (name "Net-(U1-UVF2)") (class "Default")
      (node (ref "R15") (pin "1") (pinfunction "1_1") (pintype "passive"))
      (node (ref "R7") (pin "2") (pinfunction "2_2") (pintype "passive"))
      (node (ref "U1") (pin "29") (pinfunction "UVF2_29") (pintype "input"))
    )
    (net (code "31") (name "Net-(U1-UVR1)") (class "Default")
      (node (ref "R10") (pin "2") (pinfunction "2_2") (pintype "passive"))
      (node (ref "R14") (pin "1") (pinfunction "1_1") (pintype "passive"))
      (node (ref "U1") (pin "9") (pinfunction "UVR1_9") (pintype "input"))
    )
    (net (code "32") (name "Net-(U1-UVR2)") (class "Default")
      (node (ref "R16") (pin "2") (pinfunction "2_2") (pintype "passive"))
      (node (ref "R7") (pin "1") (pinfunction "1_1") (pintype "passive"))
      (node (ref "U1") (pin "28") (pinfunction "UVR2_28") (pintype "input"))
    )
    (net (code "33") (name "OUT") (class "Default")
      (node (ref "J1") (pin "3") (pinfunction "3_3") (pintype "passive"))
      (node (ref "J1") (pin "4") (pinfunction "4_4") (pintype "passive"))
      (node (ref "TP7") (pin "1") (pinfunction "1_1") (pintype "passive"))
      (node (ref "XF2") (pin "3") (pinfunction "2_3") (pintype "passive"))
      (node (ref "XF2") (pin "4") (pinfunction "2_4") (pintype "passive"))
      (node (ref "XF3") (pin "3") (pinfunction "2_3") (pintype "passive"))
      (node (ref "XF3") (pin "4") (pinfunction "2_4") (pintype "passive"))
    )
    (net (code "34") (name "SOURCE1") (class "Default")
      (node (ref "C6") (pin "1") (pinfunction "1_1") (pintype "passive"))
      (node (ref "Q1") (pin "3") (pinfunction "S_3") (pintype "passive"))
      (node (ref "Q4") (pin "3") (pinfunction "S_3") (pintype "passive"))
      (node (ref "TP10") (pin "1") (pinfunction "1_1") (pintype "passive"))
      (node (ref "U1") (pin "5") (pinfunction "SOURCE1_5") (pintype "input"))
    )
    (net (code "35") (name "SOURCE2") (class "Default")
      (node (ref "C5") (pin "1") (pinfunction "1_1") (pintype "passive"))
      (node (ref "Q2") (pin "3") (pinfunction "S_3") (pintype "passive"))
      (node (ref "Q3") (pin "3") (pinfunction "S_3") (pintype "passive"))
      (node (ref "TP5") (pin "1") (pinfunction "1_1") (pintype "passive"))
      (node (ref "U1") (pin "32") (pinfunction "SOURCE2_32") (pintype "input"))
    )
    (net (code "36") (name "START") (class "Default")
      (node (ref "D3") (pin "A") (pinfunction "A_A") (pintype "passive"))
      (node (ref "J2") (pin "C") (pinfunction "3_C") (pintype "passive"))
      (node (ref "R1") (pin "2") (pinfunction "2_2") (pintype "passive"))
    )
    (net (code "37") (name "unconnected-(J3-Pad3)") (class "Default")
      (node (ref "J3") (pin "3") (pinfunction "3_3") (pintype "passive"))
    )
    (net (code "38") (name "unconnected-(J3-Pad4)") (class "Default")
      (node (ref "J3") (pin "4") (pinfunction "4_4") (pintype "passive"))
    )
    (net (code "39") (name "unconnected-(U1-CASOUT-Pad18)") (class "Default")
      (node (ref "U1") (pin "18") (pinfunction "CASOUT_18") (pintype "output"))
    )
    (net (code "40") (name "~{SHDN}") (class "Default")
      (node (ref "D2") (pin "C") (pinfunction "C_C") (pintype "passive"))
      (node (ref "D3") (pin "C") (pinfunction "C_C") (pintype "passive"))
      (node (ref "K1") (pin "3") (pinfunction "CONTROL+_3") (pintype "passive"))
      (node (ref "R3") (pin "2") (pinfunction "2_2") (pintype "passive"))
      (node (ref "TP11") (pin "1") (pinfunction "1_1") (pintype "passive"))
      (node (ref "U1") (pin "12") (pinfunction "~{DISABLE1}_12") (pintype "input"))
      (node (ref "U1") (pin "21") (pinfunction "~{SHDN}_21") (pintype "input"))
      (node (ref "U1") (pin "25") (pinfunction "~{DISABLE2}_25") (pintype "input"))
    )
  )
)
